# 2-Power.net
KiCad netlist of a schematic drawn in Altium Designer
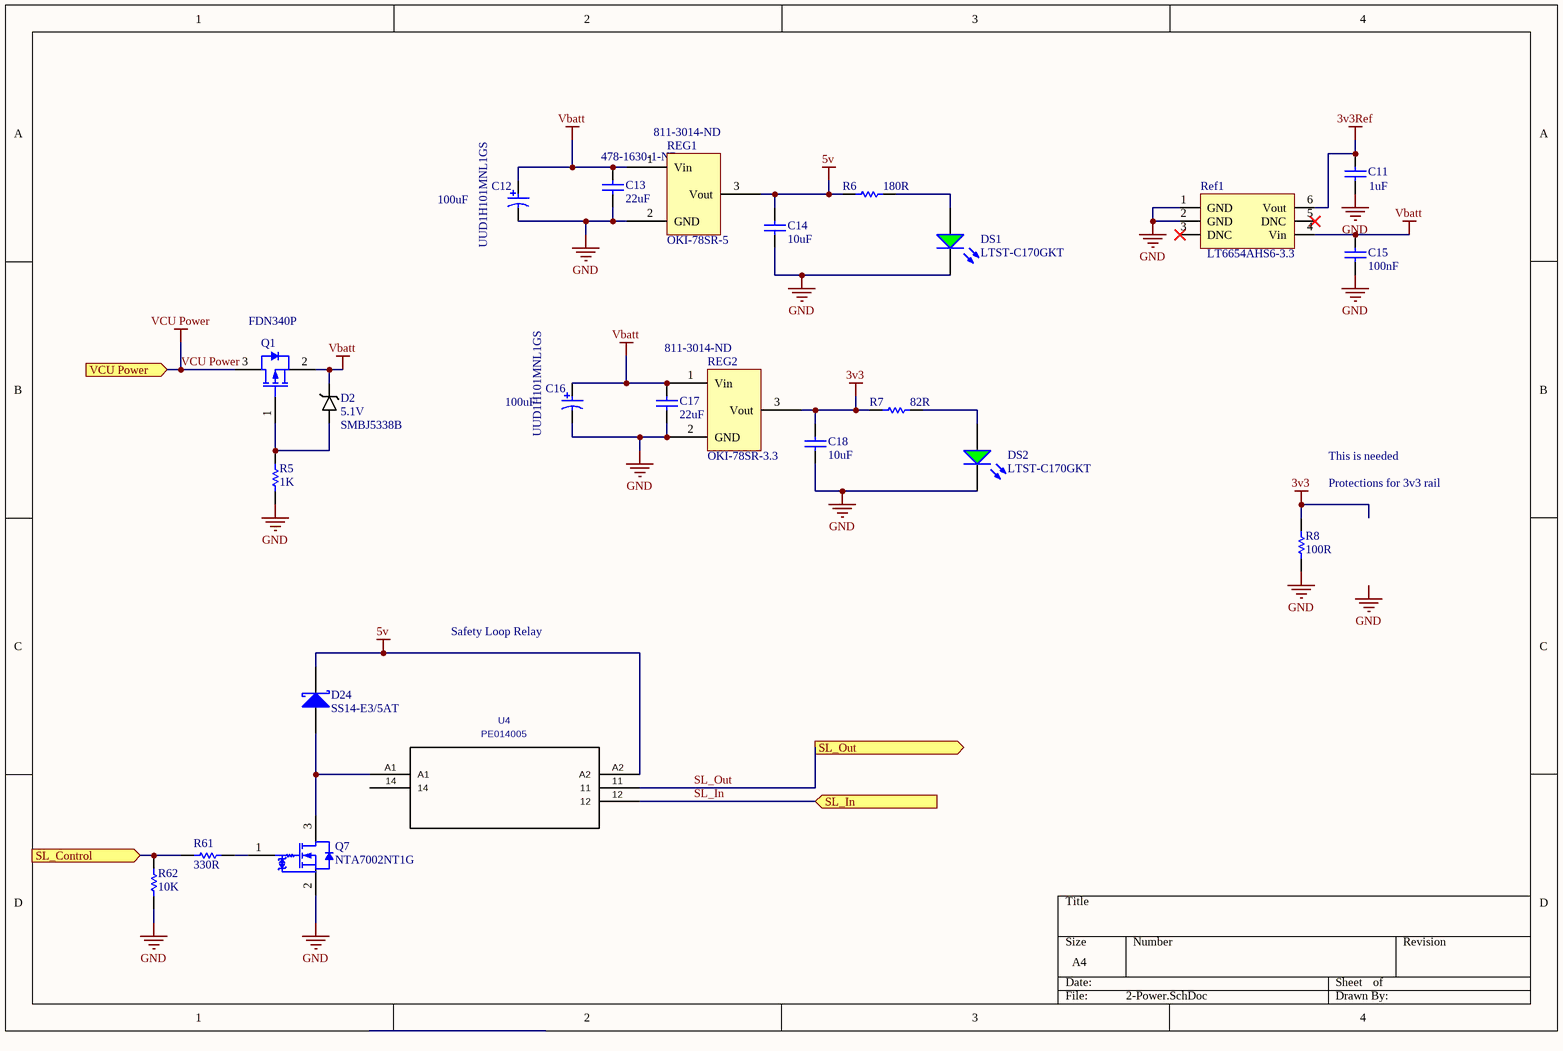
[diagram p0: 2-Power.SchDoc]

(export (version "E")
  (design (tool "Eeschema 10.0.6"))
  (components
    (comp (ref "C11")
      (value "1uF")
      (footprint "1608[0603]")
      (description "Capacitor")
      (fields
        (field (name "MANUFACTURER") "Murata Electronics North America")
        (field (name "MANUFACTURER PART NUMBER") "GRM188R61E105KA12D")
      )
      (libsource (lib "Miscellaneous Devices") (part "Cap"))
    )
    (comp (ref "C12")
      (value "UUD1H101MNL1GS")
      (footprint "NIC-CAPA2-8X10_V")
      (fields (field (name "MANUFACTURER") "Nichicon") (field (name "TOLERANCE") "±20%"))
      (libsource (lib "Altium Content Vault") (part "NIC-CAP-P-2"))
    )
    (comp (ref "C13")
      (value "22uF")
      (footprint "C1210_M")
      (description "Capacitor")
      (fields
        (field (name "MANUFACTURER") "Yageo")
        (field (name "MANUFACTURER PART NUMBER") "CC1210MKX5R8BB226")
        (field (name "SUPPLIER PART NUMBER 1") "478-1630-1-ND")
      )
      (libsource (lib "Miscellaneous Devices") (part "Cap"))
    )
    (comp (ref "C14")
      (value "10uF")
      (footprint "C1210_M")
      (description "Capacitor")
      (fields
        (field (name "MANUFACTURER") "Yageo")
        (field (name "MANUFACTURER PART NUMBER") "CC1210ZKY5V8BB106")
      )
      (libsource (lib "Miscellaneous Devices") (part "Cap"))
    )
    (comp (ref "C15")
      (value "100nF")
      (footprint "1608[0603]")
      (description "Capacitor")
      (fields
        (field (name "MANUFACTURER") "Yageo")
        (field (name "MANUFACTURER PART NUMBER") "CC0603KRX7R9BB104")
      )
      (libsource (lib "Miscellaneous Devices") (part "Cap"))
    )
    (comp (ref "C16")
      (value "UUD1H101MNL1GS")
      (footprint "NIC-CAPA2-8X10_V")
      (fields (field (name "MANUFACTURER") "Nichicon") (field (name "TOLERANCE") "±20%"))
      (libsource (lib "Altium Content Vault") (part "NIC-CAP-P-2"))
    )
    (comp (ref "C17")
      (value "22uF")
      (footprint "C1210_M")
      (description "Capacitor")
      (fields
        (field (name "MANUFACTURER") "Yageo")
        (field (name "MANUFACTURER PART NUMBER") "CC1210MKX5R8BB226")
      )
      (libsource (lib "Miscellaneous Devices") (part "Cap"))
    )
    (comp (ref "C18")
      (value "10uF")
      (footprint "C1210_M")
      (description "Capacitor")
      (fields
        (field (name "MANUFACTURER") "Yageo")
        (field (name "MANUFACTURER PART NUMBER") "CC1210ZKY5V8BB106")
      )
      (libsource (lib "Miscellaneous Devices") (part "Cap"))
    )
    (comp (ref "D2")
      (value "Zener Diode, 5.1V, 5W SMBJ5338B")
      (footprint "DO-214AA (SMB)")
      (fields
        (field (name "POWER") "5W")
        (field (name "REVERSE VOLTAGE") "5.1V")
        (field (name "PART NUMBER") "SMBJ5338B")
      )
      (libsource (lib "VCU Library") (part "Zener Diode, 5.1V, 5W SMBJ5338B"))
    )
    (comp (ref "D24")
      (value "SS14-E3/5AT")
      (footprint "VISH-DO-214AC-2_V")
      (fields (field (name "MANUFACTURER") "Vishay Semiconductor"))
      (libsource (lib "Altium Content Vault") (part "VISH-DSKY_A1K2-2"))
    )
    (comp (ref "DS1")
      (value "LTST-C170GKT")
      (footprint "LTST-C170GKT_V")
      (description "LED Uni-Color Green, 100 mW, 120 mA, -55 to 85 degC, 2-Pin SMD, RoHS, Tape and Reel")
      (fields (field (name "MANUFACTURER") "Lite-On"))
      (libsource (lib "Altium Content Vault") (part "LED-GREEN-AK-2"))
    )
    (comp (ref "DS2")
      (value "LTST-C170GKT")
      (footprint "LTST-C170GKT_V")
      (description "LED Uni-Color Green, 100 mW, 120 mA, -55 to 85 degC, 2-Pin SMD, RoHS, Tape and Reel")
      (fields (field (name "MANUFACTURER") "Lite-On"))
      (libsource (lib "Altium Content Vault") (part "LED-GREEN-AK-2"))
    )
    (comp (ref "Q1")
      (value "FDN340P")
      (footprint "FAIR-SSOT3L-3_V")
      (fields (field (name "MANUFACTURER") "Fairchild Semiconductor"))
      (libsource (lib "Altium Content Vault") (part "PEMOS-GSD-3"))
    )
    (comp (ref "Q7")
      (value "NTA7002NT1G")
      (footprint "ONSC-SC-75-3-463-01_V")
      (fields (field (name "MANUFACTURER") "On Semiconductor"))
      (libsource (lib "Altium Content Vault") (part "ONSC-NMOS-G1S2D3-3_D"))
    )
    (comp (ref "R5")
      (value "1K")
      (footprint "1608[0603]")
      (description "Resistor")
      (fields
        (field (name "MANUFACTURER") "Panasonic Electronic Components")
        (field (name "MANUFACTURER PART NUMBER") "ERJ-PA3F1001V")
      )
      (libsource (lib "Miscellaneous Devices") (part "Res1"))
    )
    (comp (ref "R6")
      (value "180R")
      (footprint "1608[0603]")
      (description "Resistor")
      (fields
        (field (name "MANUFACTURER") "Yageo")
        (field (name "MANUFACTURER PART NUMBER") "RC0603JR-07180RL")
      )
      (libsource (lib "Miscellaneous Devices") (part "Res1"))
    )
    (comp (ref "R7")
      (value "82R")
      (footprint "1608[0603]")
      (description "Resistor")
      (fields
        (field (name "MANUFACTURER") "Yageo")
        (field (name "MANUFACTURER PART NUMBER") "RC0603JR-0782RL")
      )
      (libsource (lib "Miscellaneous Devices") (part "Res1"))
    )
    (comp (ref "R8")
      (value "100R")
      (footprint "RESC1206(3216)_M")
      (description "100R 0.25W 5% 1206 (3216 Metric)  SMD")
      (fields (field (name "TOLERANCE") "5 %") (field (name "POWER") "0.25 W"))
      (libsource (lib "Altium Content Vault") (part "RES"))
    )
    (comp (ref "R61")
      (value "330R")
      (footprint "1608[0603]")
      (description "Resistor")
      (fields
        (field (name "MANUFACTURER") "Panasonic Electronic Components")
        (field (name "MANUFACTURER PART NUMBER") "ERJ-PA3F1001V")
      )
      (libsource (lib "Miscellaneous Devices") (part "Res1"))
    )
    (comp (ref "R62")
      (value "10K")
      (footprint "1608[0603]")
      (description "Resistor")
      (fields
        (field (name "MANUFACTURER") "Panasonic Electronic Components")
        (field (name "MANUFACTURER PART NUMBER") "ERJ-PA3F1001V")
      )
      (libsource (lib "Miscellaneous Devices") (part "Res1"))
    )
    (comp (ref "Ref1")
      (value "LT6654AHS6-3.3")
      (footprint "TSOT-23 S6")
      (fields
        (field (name "DIGIKEY PART NUMBER") "LT6654AHS6-3.3#TRMPBFCT-ND")
        (field (name "MANUFACTURER") "Linear Technology")
        (field (name "TOLERANCE") "±0.05%")
      )
      (libsource (lib "VCU Library") (part "LT6654AHS6-3.3"))
    )
    (comp (ref "REG1")
      (value "OKI-78SR-5")
      (footprint "OKI-78SR-5/1.5-W - Horizontal")
      (description "5V DCDC")
      (fields
        (field (name "SUPPLIER PART NUMBER 2") "811-3014-ND")
        (field (name "MANUFACTURER") "Murata Power Solutions Inc.")
        (field (name "MANUFACTURER PART NUMBER") "OKI-78SR-3.3/1.5-W36H-C")
      )
      (libsource (lib "FE Schem Lib") (part "OKI-78SR-5"))
    )
    (comp (ref "REG2")
      (value "OKI-78SR-3.3")
      (footprint "Reg - TH, 3 pin, 100 mil Pitch, VTL")
      (description "3.3V DCDC")
      (fields
        (field (name "SUPPLIER PART NUMBER 2") "811-3014-ND")
        (field (name "MANUFACTURER") "Murata Power Solutions Inc.")
        (field (name "MANUFACTURER PART NUMBER") "OKI-78SR-3.3/1.5-W36H-C")
      )
      (libsource (lib "FE Schem Lib") (part "OKI-78SR-5"))
    )
    (comp (ref "U4")
      (value "PE014005")
      (footprint "PE014005")
      (fields (field (name "COPYRIGHT") "Copyright (C) 2021 Ultra Librarian. All rights reserved."))
      (libsource (lib "AltiumV15") (part "PE014005"))
    )
  )
  (nets
    (net (code "1") (name "/SL_Control") (class "Default")
      (node (ref "R61") (pin "2") (pinfunction "2_2") (pintype "passive"))
      (node (ref "R62") (pin "2") (pinfunction "2_2") (pintype "passive"))
    )
    (net (code "2") (name "/SL_In") (class "Default")
      (node (ref "U4") (pin "12") (pinfunction "12_12") (pintype "passive"))
    )
    (net (code "3") (name "/SL_Out") (class "Default")
      (node (ref "U4") (pin "11") (pinfunction "11_11") (pintype "passive"))
    )
    (net (code "4") (name "3v3") (class "Default")
      (node (ref "C18") (pin "2") (pinfunction "2_2") (pintype "passive"))
      (node (ref "R7") (pin "1") (pinfunction "1_1") (pintype "passive"))
      (node (ref "R8") (pin "2") (pinfunction "2_2") (pintype "passive"))
      (node (ref "REG2") (pin "3") (pinfunction "Vout_3") (pintype "passive"))
    )
    (net (code "5") (name "3v3Ref") (class "Default")
      (node (ref "C11") (pin "2") (pinfunction "2_2") (pintype "passive"))
      (node (ref "Ref1") (pin "6") (pinfunction "Vout_6") (pintype "passive"))
    )
    (net (code "6") (name "5v") (class "Default")
      (node (ref "C14") (pin "2") (pinfunction "2_2") (pintype "passive"))
      (node (ref "D24") (pin "2") (pinfunction "K_2") (pintype "passive"))
      (node (ref "R6") (pin "1") (pinfunction "1_1") (pintype "passive"))
      (node (ref "REG1") (pin "3") (pinfunction "Vout_3") (pintype "passive"))
      (node (ref "U4") (pin "A2") (pinfunction "A2_A2") (pintype "passive"))
    )
    (net (code "7") (name "GND") (class "Default")
      (node (ref "C11") (pin "1") (pinfunction "1_1") (pintype "passive"))
      (node (ref "C12") (pin "2") (pinfunction "2_2") (pintype "passive"))
      (node (ref "C13") (pin "1") (pinfunction "1_1") (pintype "passive"))
      (node (ref "C14") (pin "1") (pinfunction "1_1") (pintype "passive"))
      (node (ref "C15") (pin "1") (pinfunction "1_1") (pintype "passive"))
      (node (ref "C16") (pin "2") (pinfunction "2_2") (pintype "passive"))
      (node (ref "C17") (pin "1") (pinfunction "1_1") (pintype "passive"))
      (node (ref "C18") (pin "1") (pinfunction "1_1") (pintype "passive"))
      (node (ref "DS1") (pin "2") (pinfunction "K_2") (pintype "passive"))
      (node (ref "DS2") (pin "2") (pinfunction "K_2") (pintype "passive"))
      (node (ref "Q7") (pin "2") (pinfunction "S_2") (pintype "passive"))
      (node (ref "R5") (pin "1") (pinfunction "1_1") (pintype "passive"))
      (node (ref "R62") (pin "1") (pinfunction "1_1") (pintype "passive"))
      (node (ref "R8") (pin "1") (pinfunction "1_1") (pintype "passive"))
      (node (ref "REG1") (pin "2") (pinfunction "GND_2") (pintype "passive"))
      (node (ref "REG2") (pin "2") (pinfunction "GND_2") (pintype "passive"))
      (node (ref "Ref1") (pin "1") (pinfunction "GND_1") (pintype "passive"))
      (node (ref "Ref1") (pin "2") (pinfunction "GND_2") (pintype "passive"))
    )
    (net (code "8") (name "Net-(D2-2)") (class "Default")
      (node (ref "D2") (pin "A") (pinfunction "2_A") (pintype "passive"))
      (node (ref "Q1") (pin "1") (pinfunction "GATE_1") (pintype "passive"))
      (node (ref "R5") (pin "2") (pinfunction "2_2") (pintype "passive"))
    )
    (net (code "9") (name "Net-(D24-A)") (class "Default")
      (node (ref "D24") (pin "1") (pinfunction "A_1") (pintype "passive"))
      (node (ref "Q7") (pin "3") (pinfunction "D_3") (pintype "passive"))
      (node (ref "U4") (pin "A1") (pinfunction "A1_A1") (pintype "passive"))
    )
    (net (code "10") (name "Net-(DS1-A)") (class "Default")
      (node (ref "DS1") (pin "1") (pinfunction "A_1") (pintype "passive"))
      (node (ref "R6") (pin "2") (pinfunction "2_2") (pintype "passive"))
    )
    (net (code "11") (name "Net-(DS2-A)") (class "Default")
      (node (ref "DS2") (pin "1") (pinfunction "A_1") (pintype "passive"))
      (node (ref "R7") (pin "2") (pinfunction "2_2") (pintype "passive"))
    )
    (net (code "12") (name "Net-(Q7-G)") (class "Default")
      (node (ref "Q7") (pin "1") (pinfunction "G_1") (pintype "passive"))
      (node (ref "R61") (pin "1") (pinfunction "1_1") (pintype "passive"))
    )
    (net (code "13") (name "VCU Power") (class "Default")
      (node (ref "Q1") (pin "3") (pinfunction "DRAIN_3") (pintype "passive"))
    )
    (net (code "14") (name "Vbatt") (class "Default")
      (node (ref "C12") (pin "1") (pinfunction "1_1") (pintype "passive"))
      (node (ref "C13") (pin "2") (pinfunction "2_2") (pintype "passive"))
      (node (ref "C15") (pin "2") (pinfunction "2_2") (pintype "passive"))
      (node (ref "C16") (pin "1") (pinfunction "1_1") (pintype "passive"))
      (node (ref "C17") (pin "2") (pinfunction "2_2") (pintype "passive"))
      (node (ref "D2") (pin "K") (pinfunction "1_K") (pintype "passive"))
      (node (ref "Q1") (pin "2") (pinfunction "SOURCE_2") (pintype "passive"))
      (node (ref "REG1") (pin "1") (pinfunction "Vin_1") (pintype "passive"))
      (node (ref "REG2") (pin "1") (pinfunction "Vin_1") (pintype "passive"))
      (node (ref "Ref1") (pin "4") (pinfunction "Vin_4") (pintype "passive"))
    )
    (net (code "15") (name "unconnected-(Ref1-DNC-Pad3)") (class "Default")
      (node (ref "Ref1") (pin "3") (pinfunction "DNC_3") (pintype "passive+no_connect"))
    )
    (net (code "16") (name "unconnected-(Ref1-DNC-Pad5)") (class "Default")
      (node (ref "Ref1") (pin "5") (pinfunction "DNC_5") (pintype "passive+no_connect"))
    )
    (net (code "17") (name "unconnected-(U4-Pad14)") (class "Default")
      (node (ref "U4") (pin "14") (pinfunction "14_14") (pintype "passive"))
    )
  )
)
